# Control.net
KiCad netlist of a schematic drawn in EAGLE
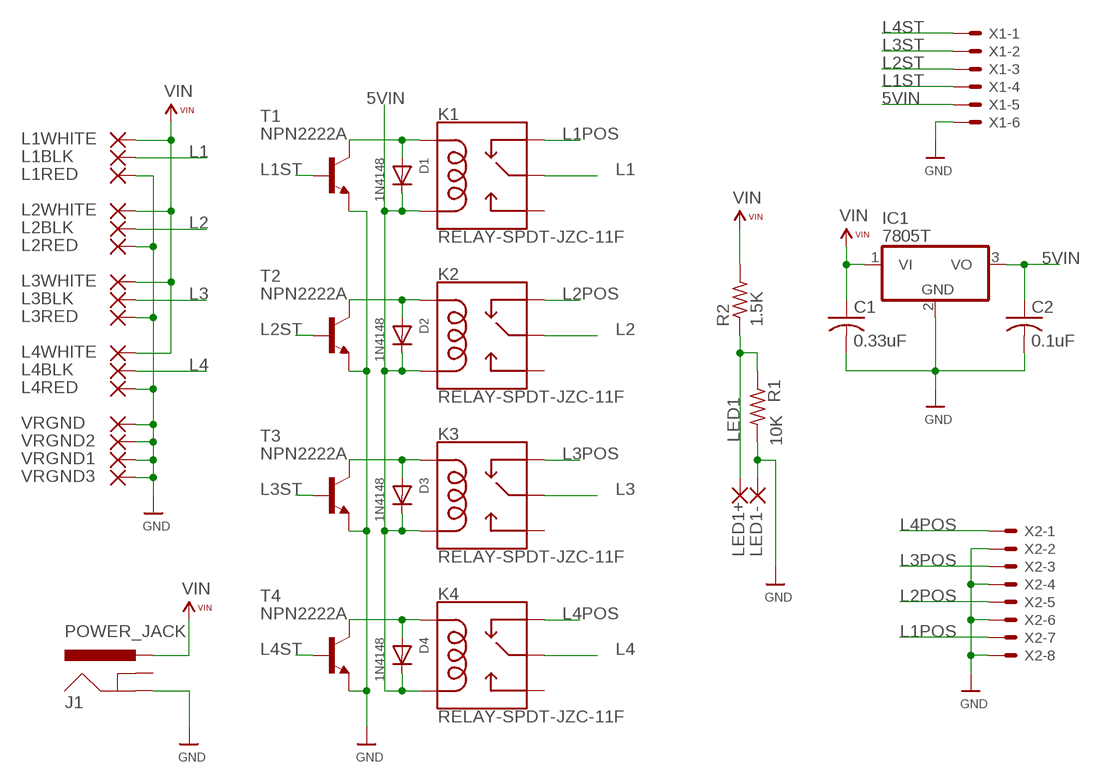
[diagram p0: schematic, sheet 1]

(export (version "E")
  (design (tool "Eeschema 10.0.6"))
  (components
    (comp (ref "C1")
      (value "0.33uF")
      (footprint "eagle-import:C1206")
      (libsource (lib "eagle-import") (part "C-USC1206"))
    )
    (comp (ref "C2")
      (value "0.1uF")
      (footprint "eagle-import:C1206")
      (libsource (lib "eagle-import") (part "C-USC1206"))
    )
    (comp (ref "D1")
      (value "1N4148")
      (footprint "eagle-import:DO-1N4148")
      (libsource (lib "eagle-import") (part "DIODEDO-1N4148"))
    )
    (comp (ref "D2")
      (value "1N4148")
      (footprint "eagle-import:DO-1N4148")
      (libsource (lib "eagle-import") (part "DIODEDO-1N4148"))
    )
    (comp (ref "D3")
      (value "1N4148")
      (footprint "eagle-import:DO-1N4148")
      (libsource (lib "eagle-import") (part "DIODEDO-1N4148"))
    )
    (comp (ref "D4")
      (value "1N4148")
      (footprint "eagle-import:DO-1N4148")
      (libsource (lib "eagle-import") (part "DIODEDO-1N4148"))
    )
    (comp (ref "IC1")
      (value "7805T")
      (footprint "eagle-import:TO220H")
      (libsource (lib "eagle-import") (part "78T05"))
    )
    (comp (ref "J1")
      (value "POWER_JACK")
      (footprint "eagle-import:POWER_JACK_PTH")
      (libsource (lib "eagle-import") (part "POWER_JACK"))
    )
    (comp (ref "K1")
      (value "RELAY-SPDT-JZC-11F")
      (footprint "eagle-import:RELAY-JZC")
      (libsource (lib "eagle-import") (part "RELAY-SPDT-JZC-11F"))
    )
    (comp (ref "K2")
      (value "RELAY-SPDT-JZC-11F")
      (footprint "eagle-import:RELAY-JZC")
      (libsource (lib "eagle-import") (part "RELAY-SPDT-JZC-11F"))
    )
    (comp (ref "K3")
      (value "RELAY-SPDT-JZC-11F")
      (footprint "eagle-import:RELAY-JZC")
      (libsource (lib "eagle-import") (part "RELAY-SPDT-JZC-11F"))
    )
    (comp (ref "K4")
      (value "RELAY-SPDT-JZC-11F")
      (footprint "eagle-import:RELAY-JZC")
      (libsource (lib "eagle-import") (part "RELAY-SPDT-JZC-11F"))
    )
    (comp (ref "L1BLK")
      (value "SMD5")
      (footprint "eagle-import:SMD5,5X5")
      (libsource (lib "eagle-import") (part "SMD5"))
    )
    (comp (ref "L1RED")
      (value "SMD5")
      (footprint "eagle-import:SMD5,5X5")
      (libsource (lib "eagle-import") (part "SMD5"))
    )
    (comp (ref "L1WHITE")
      (value "SMD5")
      (footprint "eagle-import:SMD5,5X5")
      (libsource (lib "eagle-import") (part "SMD5"))
    )
    (comp (ref "L2BLK")
      (value "SMD5")
      (footprint "eagle-import:SMD5,5X5")
      (libsource (lib "eagle-import") (part "SMD5"))
    )
    (comp (ref "L2RED")
      (value "SMD5")
      (footprint "eagle-import:SMD5,5X5")
      (libsource (lib "eagle-import") (part "SMD5"))
    )
    (comp (ref "L2WHITE")
      (value "SMD5")
      (footprint "eagle-import:SMD5,5X5")
      (libsource (lib "eagle-import") (part "SMD5"))
    )
    (comp (ref "L3BLK")
      (value "SMD5")
      (footprint "eagle-import:SMD5,5X5")
      (libsource (lib "eagle-import") (part "SMD5"))
    )
    (comp (ref "L3RED")
      (value "SMD5")
      (footprint "eagle-import:SMD5,5X5")
      (libsource (lib "eagle-import") (part "SMD5"))
    )
    (comp (ref "L3WHITE")
      (value "SMD5")
      (footprint "eagle-import:SMD5,5X5")
      (libsource (lib "eagle-import") (part "SMD5"))
    )
    (comp (ref "L4BLK")
      (value "SMD5")
      (footprint "eagle-import:SMD5,5X5")
      (libsource (lib "eagle-import") (part "SMD5"))
    )
    (comp (ref "L4RED")
      (value "SMD5")
      (footprint "eagle-import:SMD5,5X5")
      (libsource (lib "eagle-import") (part "SMD5"))
    )
    (comp (ref "L4WHITE")
      (value "SMD5")
      (footprint "eagle-import:SMD5,5X5")
      (libsource (lib "eagle-import") (part "SMD5"))
    )
    (comp (ref "LED1+")
      (value "SMD5")
      (footprint "eagle-import:SMD2,54-5,08")
      (libsource (lib "eagle-import") (part "wirepad_412_SMD5"))
    )
    (comp (ref "LED1-")
      (value "SMD5")
      (footprint "eagle-import:SMD2,54-5,08")
      (libsource (lib "eagle-import") (part "wirepad_412_SMD5"))
    )
    (comp (ref "R1")
      (value "10K")
      (footprint "eagle-import:M1206")
      (libsource (lib "eagle-import") (part "R-US_M1206"))
    )
    (comp (ref "R2")
      (value "1.5K")
      (footprint "eagle-import:M1206")
      (libsource (lib "eagle-import") (part "R-US_M1206"))
    )
    (comp (ref "T1")
      (value "NPN2222A")
      (footprint "eagle-import:TO92")
      (libsource (lib "eagle-import") (part "2N5088"))
    )
    (comp (ref "T2")
      (value "NPN2222A")
      (footprint "eagle-import:TO92")
      (libsource (lib "eagle-import") (part "2N5088"))
    )
    (comp (ref "T3")
      (value "NPN2222A")
      (footprint "eagle-import:TO92")
      (libsource (lib "eagle-import") (part "2N5088"))
    )
    (comp (ref "T4")
      (value "NPN2222A")
      (footprint "eagle-import:TO92")
      (libsource (lib "eagle-import") (part "2N5088"))
    )
    (comp (ref "VRGND")
      (value "SMD5")
      (footprint "eagle-import:SMD5,5X5")
      (libsource (lib "eagle-import") (part "SMD5"))
    )
    (comp (ref "VRGND1")
      (value "SMD5")
      (footprint "eagle-import:SMD5,5X5")
      (libsource (lib "eagle-import") (part "SMD5"))
    )
    (comp (ref "VRGND2")
      (value "SMD5")
      (footprint "eagle-import:SMD5,5X5")
      (libsource (lib "eagle-import") (part "SMD5"))
    )
    (comp (ref "VRGND3")
      (value "SMD5")
      (footprint "eagle-import:SMD5,5X5")
      (libsource (lib "eagle-import") (part "SMD5"))
    )
    (comp (ref "X1")
      (value "KK-156-6")
      (footprint "eagle-import:KK-156-6")
      (fields (field (name "MF") "MOLEX"))
      (libsource (lib "eagle-import") (part "KK-156-6"))
    )
    (comp (ref "X2")
      (value "KK-156-8")
      (footprint "eagle-import:KK-156-8")
      (fields (field (name "MF") "MOLEX"))
      (libsource (lib "eagle-import") (part "KK-156-8"))
    )
  )
  (nets
    (net (code "1") (name "/5VIN") (class "Default")
      (node (ref "C2") (pin "1") (pinfunction "1_1") (pintype "passive"))
      (node (ref "D1") (pin "C") (pinfunction "C_C") (pintype "passive"))
      (node (ref "D2") (pin "C") (pinfunction "C_C") (pintype "passive"))
      (node (ref "D3") (pin "C") (pinfunction "C_C") (pintype "passive"))
      (node (ref "D4") (pin "C") (pinfunction "C_C") (pintype "passive"))
      (node (ref "IC1") (pin "3") (pinfunction "VO_3") (pintype "passive"))
      (node (ref "K1") (pin "1") (pinfunction "COIL2_1") (pintype "bidirectional"))
      (node (ref "K2") (pin "1") (pinfunction "COIL2_1") (pintype "bidirectional"))
      (node (ref "K3") (pin "1") (pinfunction "COIL2_1") (pintype "bidirectional"))
      (node (ref "K4") (pin "1") (pinfunction "COIL2_1") (pintype "bidirectional"))
      (node (ref "X1") (pin "5") (pinfunction "S_5") (pintype "passive"))
    )
    (net (code "2") (name "/L1") (class "Default")
      (node (ref "K1") (pin "4") (pinfunction "MAIN_4") (pintype "bidirectional"))
      (node (ref "L1BLK") (pin "1") (pinfunction "P_1") (pintype "passive"))
    )
    (net (code "3") (name "/L1POS") (class "Default")
      (node (ref "K1") (pin "2") (pinfunction "NC_2") (pintype "bidirectional"))
      (node (ref "X2") (pin "7") (pinfunction "S_7") (pintype "passive"))
    )
    (net (code "4") (name "/L1ST") (class "Default")
      (node (ref "T1") (pin "2") (pinfunction "B_2") (pintype "passive"))
      (node (ref "X1") (pin "4") (pinfunction "S_4") (pintype "passive"))
    )
    (net (code "5") (name "/L2") (class "Default")
      (node (ref "K2") (pin "4") (pinfunction "MAIN_4") (pintype "bidirectional"))
      (node (ref "L2BLK") (pin "1") (pinfunction "P_1") (pintype "passive"))
    )
    (net (code "6") (name "/L2POS") (class "Default")
      (node (ref "K2") (pin "2") (pinfunction "NC_2") (pintype "bidirectional"))
      (node (ref "X2") (pin "5") (pinfunction "S_5") (pintype "passive"))
    )
    (net (code "7") (name "/L2ST") (class "Default")
      (node (ref "T2") (pin "2") (pinfunction "B_2") (pintype "passive"))
      (node (ref "X1") (pin "3") (pinfunction "S_3") (pintype "passive"))
    )
    (net (code "8") (name "/L3") (class "Default")
      (node (ref "K3") (pin "4") (pinfunction "MAIN_4") (pintype "bidirectional"))
      (node (ref "L3BLK") (pin "1") (pinfunction "P_1") (pintype "passive"))
    )
    (net (code "9") (name "/L3POS") (class "Default")
      (node (ref "K3") (pin "2") (pinfunction "NC_2") (pintype "bidirectional"))
      (node (ref "X2") (pin "3") (pinfunction "S_3") (pintype "passive"))
    )
    (net (code "10") (name "/L3ST") (class "Default")
      (node (ref "T3") (pin "2") (pinfunction "B_2") (pintype "passive"))
      (node (ref "X1") (pin "2") (pinfunction "S_2") (pintype "passive"))
    )
    (net (code "11") (name "/L4") (class "Default")
      (node (ref "K4") (pin "4") (pinfunction "MAIN_4") (pintype "bidirectional"))
      (node (ref "L4BLK") (pin "1") (pinfunction "P_1") (pintype "passive"))
    )
    (net (code "12") (name "/L4POS") (class "Default")
      (node (ref "K4") (pin "2") (pinfunction "NC_2") (pintype "bidirectional"))
      (node (ref "X2") (pin "1") (pinfunction "S_1") (pintype "passive"))
    )
    (net (code "13") (name "/L4ST") (class "Default")
      (node (ref "T4") (pin "2") (pinfunction "B_2") (pintype "passive"))
      (node (ref "X1") (pin "1") (pinfunction "S_1") (pintype "passive"))
    )
    (net (code "14") (name "/LED1") (class "Default")
      (node (ref "LED1+") (pin "1") (pinfunction "P_1") (pintype "passive"))
      (node (ref "R1") (pin "1") (pinfunction "1_1") (pintype "passive"))
      (node (ref "R2") (pin "1") (pinfunction "1_1") (pintype "passive"))
    )
    (net (code "15") (name "GND") (class "Default")
      (node (ref "C1") (pin "2") (pinfunction "2_2") (pintype "passive"))
      (node (ref "C2") (pin "2") (pinfunction "2_2") (pintype "passive"))
      (node (ref "IC1") (pin "2") (pinfunction "GND_2") (pintype "passive"))
      (node (ref "J1") (pin "GND") (pinfunction "GND_GND") (pintype "bidirectional"))
      (node (ref "L1RED") (pin "1") (pinfunction "P_1") (pintype "passive"))
      (node (ref "L2RED") (pin "1") (pinfunction "P_1") (pintype "passive"))
      (node (ref "L3RED") (pin "1") (pinfunction "P_1") (pintype "passive"))
      (node (ref "L4RED") (pin "1") (pinfunction "P_1") (pintype "passive"))
      (node (ref "LED1-") (pin "1") (pinfunction "P_1") (pintype "passive"))
      (node (ref "R1") (pin "2") (pinfunction "2_2") (pintype "passive"))
      (node (ref "T1") (pin "3") (pinfunction "E_3") (pintype "passive"))
      (node (ref "T2") (pin "3") (pinfunction "E_3") (pintype "passive"))
      (node (ref "T3") (pin "3") (pinfunction "E_3") (pintype "passive"))
      (node (ref "T4") (pin "3") (pinfunction "E_3") (pintype "passive"))
      (node (ref "VRGND") (pin "1") (pinfunction "P_1") (pintype "passive"))
      (node (ref "VRGND1") (pin "1") (pinfunction "P_1") (pintype "passive"))
      (node (ref "VRGND2") (pin "1") (pinfunction "P_1") (pintype "passive"))
      (node (ref "VRGND3") (pin "1") (pinfunction "P_1") (pintype "passive"))
      (node (ref "X1") (pin "6") (pinfunction "S_6") (pintype "passive"))
      (node (ref "X2") (pin "2") (pinfunction "S_2") (pintype "passive"))
      (node (ref "X2") (pin "4") (pinfunction "S_4") (pintype "passive"))
      (node (ref "X2") (pin "6") (pinfunction "S_6") (pintype "passive"))
      (node (ref "X2") (pin "8") (pinfunction "S_8") (pintype "passive"))
    )
    (net (code "16") (name "Net-(K1-COIL1)") (class "Default")
      (node (ref "D1") (pin "A") (pinfunction "A_A") (pintype "passive"))
      (node (ref "K1") (pin "5") (pinfunction "COIL1_5") (pintype "bidirectional"))
      (node (ref "T1") (pin "1") (pinfunction "C_1") (pintype "passive"))
    )
    (net (code "17") (name "Net-(K2-COIL1)") (class "Default")
      (node (ref "D2") (pin "A") (pinfunction "A_A") (pintype "passive"))
      (node (ref "K2") (pin "5") (pinfunction "COIL1_5") (pintype "bidirectional"))
      (node (ref "T2") (pin "1") (pinfunction "C_1") (pintype "passive"))
    )
    (net (code "18") (name "Net-(K3-COIL1)") (class "Default")
      (node (ref "D3") (pin "A") (pinfunction "A_A") (pintype "passive"))
      (node (ref "K3") (pin "5") (pinfunction "COIL1_5") (pintype "bidirectional"))
      (node (ref "T3") (pin "1") (pinfunction "C_1") (pintype "passive"))
    )
    (net (code "19") (name "Net-(K4-COIL1)") (class "Default")
      (node (ref "D4") (pin "A") (pinfunction "A_A") (pintype "passive"))
      (node (ref "K4") (pin "5") (pinfunction "COIL1_5") (pintype "bidirectional"))
      (node (ref "T4") (pin "1") (pinfunction "C_1") (pintype "passive"))
    )
    (net (code "20") (name "VIN") (class "Default")
      (node (ref "C1") (pin "1") (pinfunction "1_1") (pintype "passive"))
      (node (ref "IC1") (pin "1") (pinfunction "VI_1") (pintype "input"))
      (node (ref "J1") (pin "PWR") (pinfunction "PWR_PWR") (pintype "bidirectional"))
      (node (ref "L1WHITE") (pin "1") (pinfunction "P_1") (pintype "passive"))
      (node (ref "L2WHITE") (pin "1") (pinfunction "P_1") (pintype "passive"))
      (node (ref "L3WHITE") (pin "1") (pinfunction "P_1") (pintype "passive"))
      (node (ref "L4WHITE") (pin "1") (pinfunction "P_1") (pintype "passive"))
      (node (ref "R2") (pin "2") (pinfunction "2_2") (pintype "passive"))
    )
    (net (code "21") (name "unconnected-(J1-PadGNDBREAK)") (class "Default")
      (node (ref "J1") (pin "GNDBREAK") (pinfunction "GNDBREAK_GNDBREAK") (pintype "bidirectional"))
    )
    (net (code "22") (name "unconnected-(K1-NO-Pad3)") (class "Default")
      (node (ref "K1") (pin "3") (pinfunction "NO_3") (pintype "bidirectional"))
    )
    (net (code "23") (name "unconnected-(K2-NO-Pad3)") (class "Default")
      (node (ref "K2") (pin "3") (pinfunction "NO_3") (pintype "bidirectional"))
    )
    (net (code "24") (name "unconnected-(K3-NO-Pad3)") (class "Default")
      (node (ref "K3") (pin "3") (pinfunction "NO_3") (pintype "bidirectional"))
    )
    (net (code "25") (name "unconnected-(K4-NO-Pad3)") (class "Default")
      (node (ref "K4") (pin "3") (pinfunction "NO_3") (pintype "bidirectional"))
    )
  )
)
